# AK9753_Human_Movement_Sensor.net
KiCad netlist of a schematic drawn in EAGLE
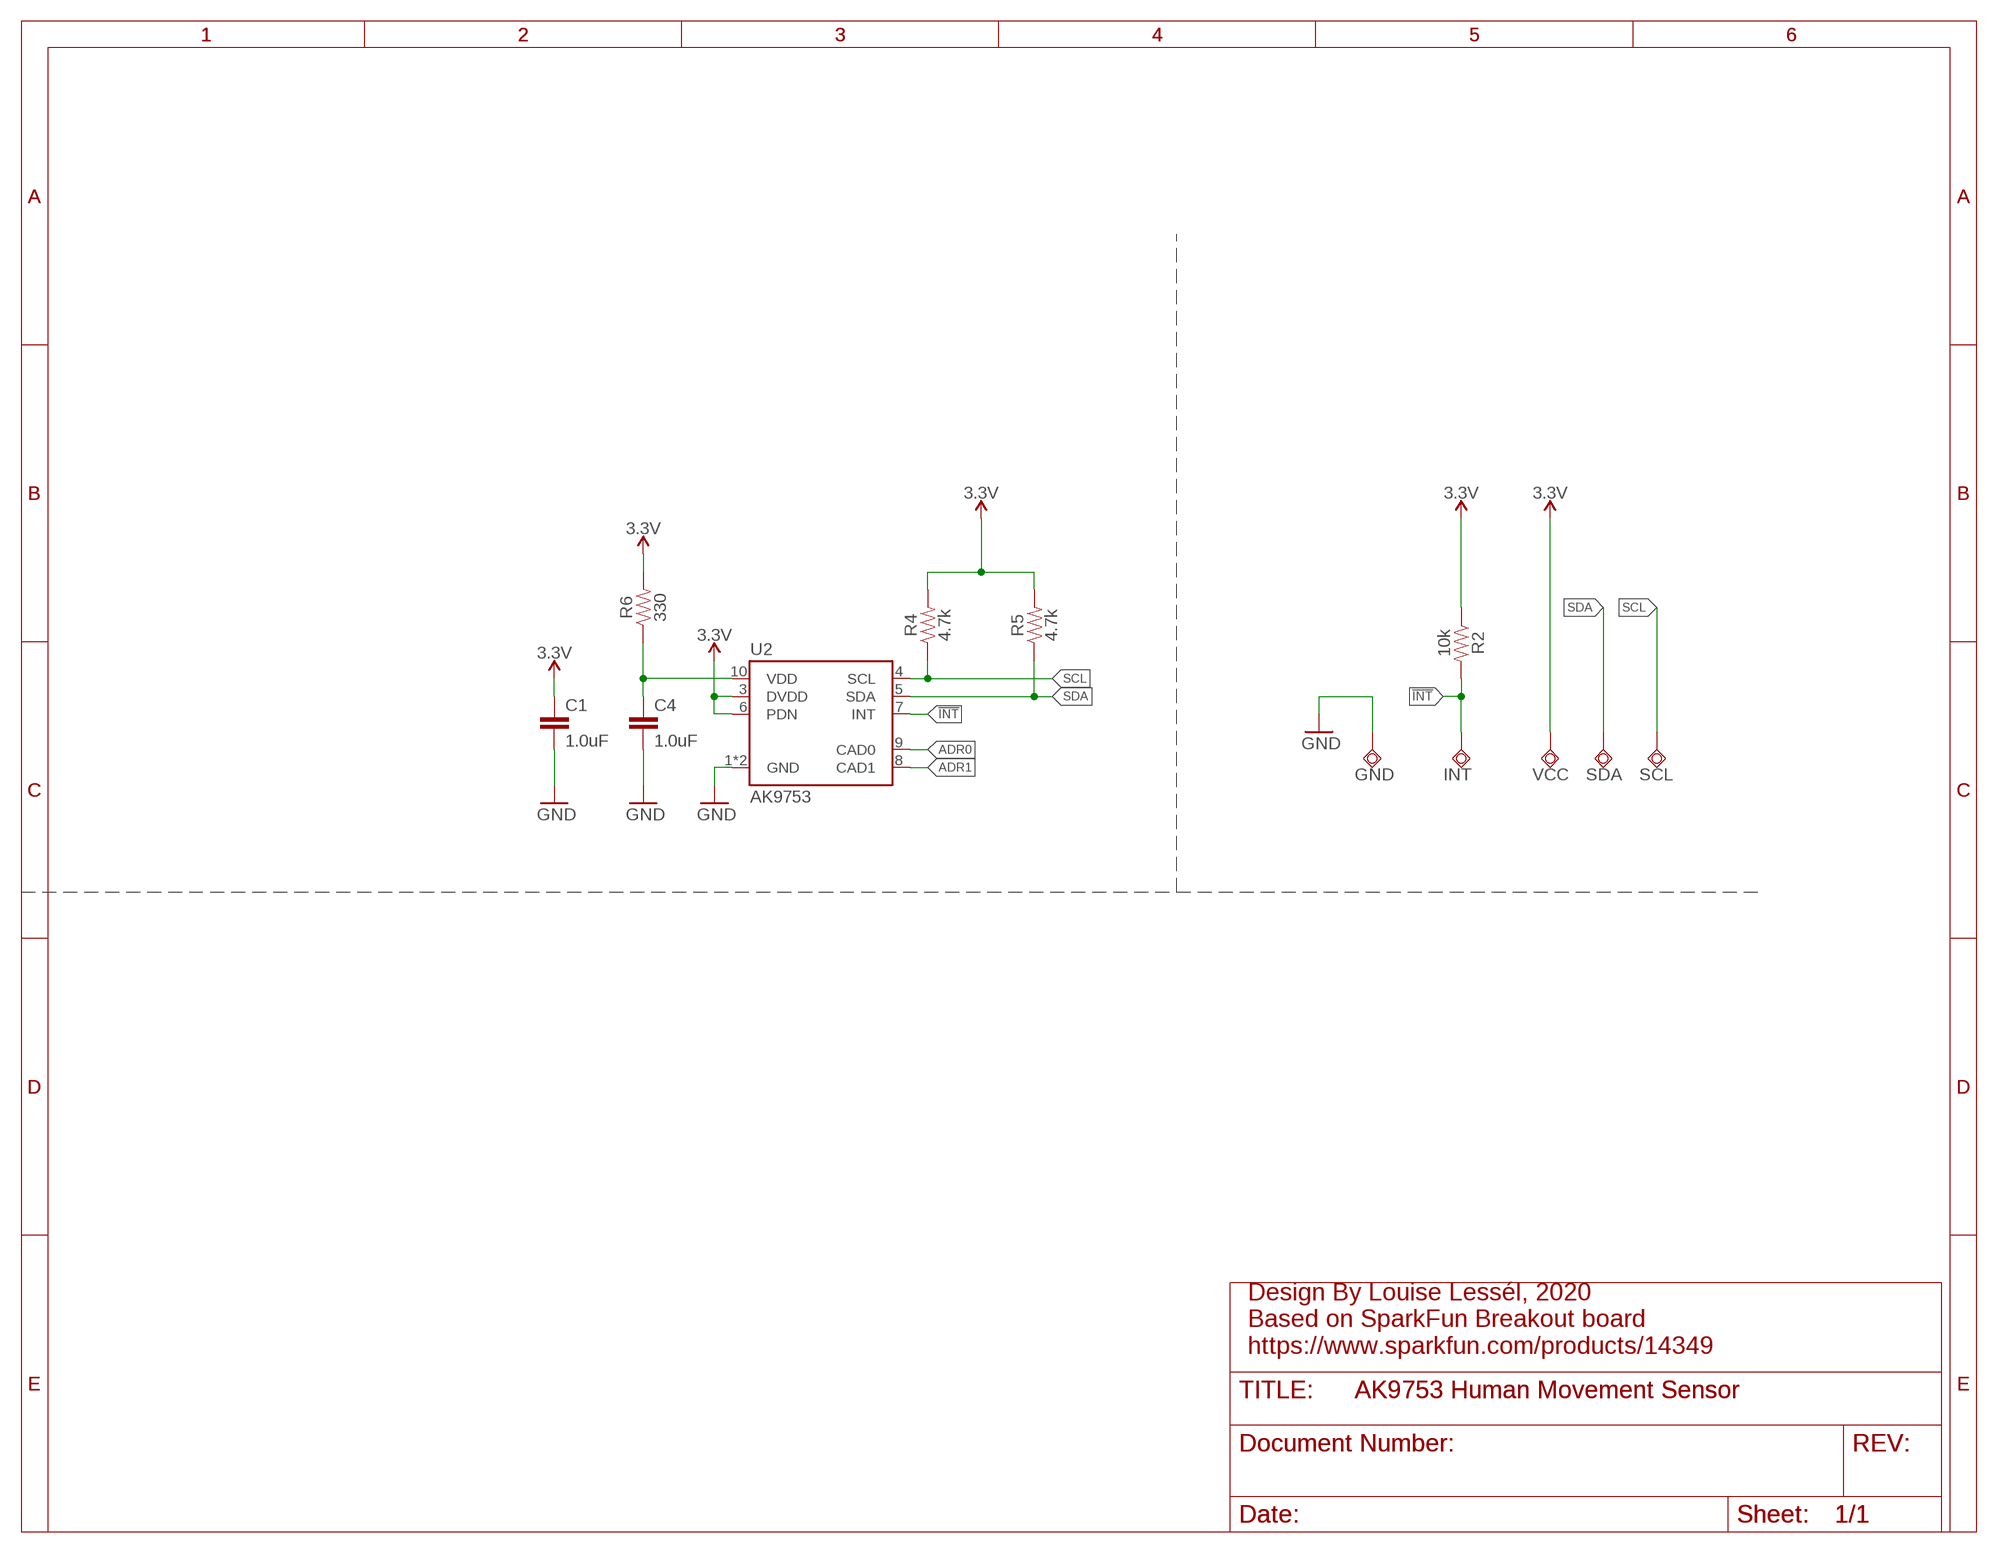
[diagram p0: schematic, sheet 1]

(export (version "E")
  (design (tool "Eeschema 10.0.6"))
  (components
    (comp (ref "C1")
      (value "1.0uF")
      (footprint "eagle-import:0603")
      (libsource (lib "eagle-import") (part "1.0UF-0603-16V-10%"))
    )
    (comp (ref "C4")
      (value "1.0uF")
      (footprint "eagle-import:0603")
      (libsource (lib "eagle-import") (part "1.0UF-0603-16V-10%"))
    )
    (comp (ref "GND")
      (value "TPSQTP20R")
      (footprint "eagle-import:TP20R")
      (libsource (lib "eagle-import") (part "TPSQTP20R"))
    )
    (comp (ref "INT")
      (value "TPSQTP20R")
      (footprint "eagle-import:TP20R")
      (libsource (lib "eagle-import") (part "TPSQTP20R"))
    )
    (comp (ref "R2")
      (value "10k")
      (footprint "eagle-import:0603")
      (libsource (lib "eagle-import") (part "10KOHM-0603-1/10W-1%"))
    )
    (comp (ref "R4")
      (value "4.7k")
      (footprint "eagle-import:0603")
      (libsource (lib "eagle-import") (part "4.7KOHM-0603-1/10W-1%"))
    )
    (comp (ref "R5")
      (value "4.7k")
      (footprint "eagle-import:0603")
      (libsource (lib "eagle-import") (part "4.7KOHM-0603-1/10W-1%"))
    )
    (comp (ref "R6")
      (value "330")
      (footprint "eagle-import:0603")
      (libsource (lib "eagle-import") (part "330OHM-0603-1/10W-1%"))
    )
    (comp (ref "SCL")
      (value "TPSQTP20R")
      (footprint "eagle-import:TP20R")
      (libsource (lib "eagle-import") (part "TPSQTP20R"))
    )
    (comp (ref "SDA")
      (value "TPSQTP20R")
      (footprint "eagle-import:TP20R")
      (libsource (lib "eagle-import") (part "TPSQTP20R"))
    )
    (comp (ref "U2")
      (value "AK9753")
      (footprint "eagle-import:SON10")
      (libsource (lib "eagle-import") (part "AK9750{dblquote}"))
    )
    (comp (ref "VCC")
      (value "TPSQTP20R")
      (footprint "eagle-import:TP20R")
      (libsource (lib "eagle-import") (part "TPSQTP20R"))
    )
  )
  (nets
    (net (code "1") (name "/~{INT}") (class "Default")
      (node (ref "INT") (pin "TP") (pinfunction "TP_TP") (pintype "input"))
      (node (ref "R2") (pin "2") (pinfunction "2_2") (pintype "passive"))
      (node (ref "U2") (pin "7") (pinfunction "INT_7") (pintype "bidirectional"))
    )
    (net (code "2") (name "3.3V") (class "Default")
      (node (ref "C1") (pin "1") (pinfunction "1_1") (pintype "passive"))
      (node (ref "R2") (pin "1") (pinfunction "1_1") (pintype "passive"))
      (node (ref "R4") (pin "2") (pinfunction "2_2") (pintype "passive"))
      (node (ref "R5") (pin "2") (pinfunction "2_2") (pintype "passive"))
      (node (ref "R6") (pin "2") (pinfunction "2_2") (pintype "passive"))
      (node (ref "U2") (pin "3") (pinfunction "DVDD_3") (pintype "bidirectional"))
      (node (ref "U2") (pin "6") (pinfunction "PDN_6") (pintype "bidirectional"))
      (node (ref "VCC") (pin "TP") (pinfunction "TP_TP") (pintype "input"))
    )
    (net (code "3") (name "ADR0") (class "Default")
      (node (ref "U2") (pin "9") (pinfunction "CAD0_9") (pintype "bidirectional"))
    )
    (net (code "4") (name "ADR1") (class "Default")
      (node (ref "U2") (pin "8") (pinfunction "CAD1_8") (pintype "bidirectional"))
    )
    (net (code "5") (name "GND") (class "Default")
      (node (ref "C1") (pin "2") (pinfunction "2_2") (pintype "passive"))
      (node (ref "C4") (pin "2") (pinfunction "2_2") (pintype "passive"))
      (node (ref "GND") (pin "TP") (pinfunction "TP_TP") (pintype "input"))
      (node (ref "U2") (pin "1") (pinfunction "GND_1") (pintype "bidirectional"))
      (node (ref "U2") (pin "2") (pinfunction "GND_2") (pintype "bidirectional"))
    )
    (net (code "6") (name "Net-(U2-VDD)") (class "Default")
      (node (ref "C4") (pin "1") (pinfunction "1_1") (pintype "passive"))
      (node (ref "R6") (pin "1") (pinfunction "1_1") (pintype "passive"))
      (node (ref "U2") (pin "10") (pinfunction "VDD_10") (pintype "bidirectional"))
    )
    (net (code "7") (name "SCL") (class "Default")
      (node (ref "R4") (pin "1") (pinfunction "1_1") (pintype "passive"))
      (node (ref "SCL") (pin "TP") (pinfunction "TP_TP") (pintype "input"))
      (node (ref "U2") (pin "4") (pinfunction "SCL_4") (pintype "bidirectional"))
    )
    (net (code "8") (name "SDA") (class "Default")
      (node (ref "R5") (pin "1") (pinfunction "1_1") (pintype "passive"))
      (node (ref "SDA") (pin "TP") (pinfunction "TP_TP") (pintype "input"))
      (node (ref "U2") (pin "5") (pinfunction "SDA_5") (pintype "bidirectional"))
    )
  )
)
